# Canaux.net
KiCad netlist of a schematic drawn in Altium Designer
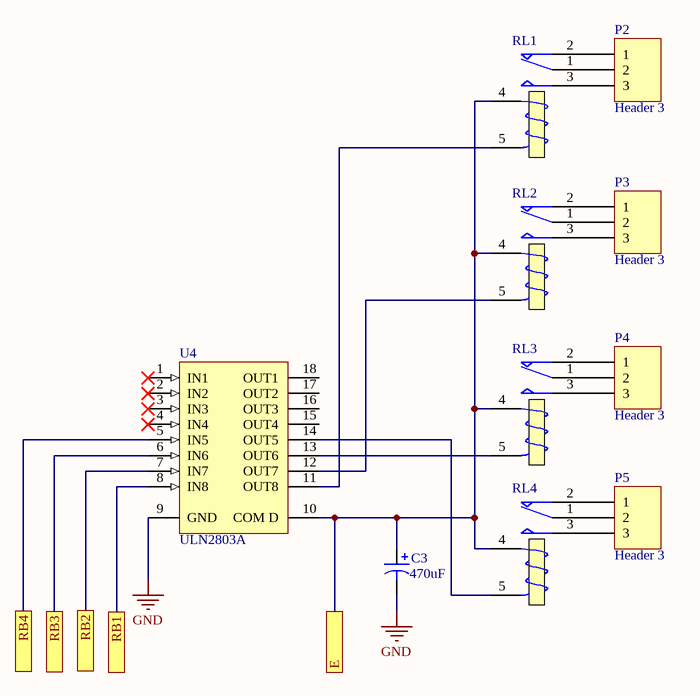
[diagram p0: Canaux.SchDoc]

(export (version "E")
  (design (tool "Eeschema 10.0.6"))
  (components
    (comp (ref "C3")
      (value "470uF")
      (footprint "RB7.6-15")
      (description "Polarized Capacitor (Radial)")
      (fields (field (name "Comment") "Cap Pol1") (field (name "PUBLISHER") "Altium Limited"))
      (libsource (lib "Miscellaneous Devices") (part "Cap Pol1"))
    )
    (comp (ref "P2")
      (value "Header 3")
      (footprint "HDR1X3")
      (description "Header, 3-Pin")
      (fields (field (name "PUBLISHER") "Altium Limited"))
      (libsource (lib "Miscellaneous Connectors") (part "Header 3"))
    )
    (comp (ref "P3")
      (value "Header 3")
      (footprint "HDR1X3")
      (description "Header, 3-Pin")
      (fields (field (name "PUBLISHER") "Altium Limited"))
      (libsource (lib "Miscellaneous Connectors") (part "Header 3"))
    )
    (comp (ref "P4")
      (value "Header 3")
      (footprint "HDR1X3")
      (description "Header, 3-Pin")
      (fields (field (name "PUBLISHER") "Altium Limited"))
      (libsource (lib "Miscellaneous Connectors") (part "Header 3"))
    )
    (comp (ref "P5")
      (value "Header 3")
      (footprint "HDR1X3")
      (description "Header, 3-Pin")
      (fields (field (name "PUBLISHER") "Altium Limited"))
      (libsource (lib "Miscellaneous Connectors") (part "Header 3"))
    )
    (comp (ref "RL1")
      (value "Relay")
      (footprint "MODULE5B")
      (description "SPDT Relay")
      (fields (field (name "PUBLISHER") "Altium Limited"))
      (libsource (lib "Miscellaneous Devices") (part "Relay"))
    )
    (comp (ref "RL2")
      (value "Relay")
      (footprint "MODULE5B")
      (description "SPDT Relay")
      (fields (field (name "PUBLISHER") "Altium Limited"))
      (libsource (lib "Miscellaneous Devices") (part "Relay"))
    )
    (comp (ref "RL3")
      (value "Relay")
      (footprint "MODULE5B")
      (description "SPDT Relay")
      (fields (field (name "PUBLISHER") "Altium Limited"))
      (libsource (lib "Miscellaneous Devices") (part "Relay"))
    )
    (comp (ref "RL4")
      (value "Relay")
      (footprint "MODULE5B")
      (description "SPDT Relay")
      (fields (field (name "PUBLISHER") "Altium Limited"))
      (libsource (lib "Miscellaneous Devices") (part "Relay"))
    )
    (comp (ref "U4")
      (value "ULN2803A")
      (footprint "A18")
      (description "High-Voltage, High-Current Darlington Array")
      (fields (field (name "PUBLISHER") "Altium Limited"))
      (libsource (lib "Allegro Interface Darlington Driver") (part "ULN2803A"))
    )
  )
  (nets
    (net (code "1") (name "/E") (class "Default")
      (node (ref "C3") (pin "1") (pinfunction "1_1") (pintype "passive"))
      (node (ref "RL1") (pin "4") (pinfunction "T1_4") (pintype "passive"))
      (node (ref "RL2") (pin "4") (pinfunction "T1_4") (pintype "passive"))
      (node (ref "RL3") (pin "4") (pinfunction "T1_4") (pintype "passive"))
      (node (ref "RL4") (pin "4") (pinfunction "T1_4") (pintype "passive"))
      (node (ref "U4") (pin "10") (pinfunction "COM_D_10") (pintype "passive"))
    )
    (net (code "2") (name "/RB1") (class "Default")
      (node (ref "U4") (pin "8") (pinfunction "IN8_8") (pintype "input"))
    )
    (net (code "3") (name "/RB2") (class "Default")
      (node (ref "U4") (pin "7") (pinfunction "IN7_7") (pintype "input"))
    )
    (net (code "4") (name "/RB3") (class "Default")
      (node (ref "U4") (pin "6") (pinfunction "IN6_6") (pintype "input"))
    )
    (net (code "5") (name "/RB4") (class "Default")
      (node (ref "U4") (pin "5") (pinfunction "IN5_5") (pintype "input"))
    )
    (net (code "6") (name "GND") (class "Default")
      (node (ref "C3") (pin "2") (pinfunction "2_2") (pintype "passive"))
      (node (ref "U4") (pin "9") (pinfunction "GND_9") (pintype "power_in"))
    )
    (net (code "7") (name "Net-(RL1-COM)") (class "Default")
      (node (ref "P2") (pin "2") (pinfunction "2_2") (pintype "passive"))
      (node (ref "RL1") (pin "1") (pinfunction "COM_1") (pintype "passive"))
    )
    (net (code "8") (name "Net-(RL1-NC)") (class "Default")
      (node (ref "P2") (pin "1") (pinfunction "1_1") (pintype "passive"))
      (node (ref "RL1") (pin "2") (pinfunction "NC_2") (pintype "passive"))
    )
    (net (code "9") (name "Net-(RL1-NO)") (class "Default")
      (node (ref "P2") (pin "3") (pinfunction "3_3") (pintype "passive"))
      (node (ref "RL1") (pin "3") (pinfunction "NO_3") (pintype "passive"))
    )
    (net (code "10") (name "Net-(RL1-T2)") (class "Default")
      (node (ref "RL1") (pin "5") (pinfunction "T2_5") (pintype "passive"))
      (node (ref "U4") (pin "11") (pinfunction "OUT8_11") (pintype "open_collector"))
    )
    (net (code "11") (name "Net-(RL2-COM)") (class "Default")
      (node (ref "P3") (pin "2") (pinfunction "2_2") (pintype "passive"))
      (node (ref "RL2") (pin "1") (pinfunction "COM_1") (pintype "passive"))
    )
    (net (code "12") (name "Net-(RL2-NC)") (class "Default")
      (node (ref "P3") (pin "1") (pinfunction "1_1") (pintype "passive"))
      (node (ref "RL2") (pin "2") (pinfunction "NC_2") (pintype "passive"))
    )
    (net (code "13") (name "Net-(RL2-NO)") (class "Default")
      (node (ref "P3") (pin "3") (pinfunction "3_3") (pintype "passive"))
      (node (ref "RL2") (pin "3") (pinfunction "NO_3") (pintype "passive"))
    )
    (net (code "14") (name "Net-(RL2-T2)") (class "Default")
      (node (ref "RL2") (pin "5") (pinfunction "T2_5") (pintype "passive"))
      (node (ref "U4") (pin "12") (pinfunction "OUT7_12") (pintype "open_collector"))
    )
    (net (code "15") (name "Net-(RL3-COM)") (class "Default")
      (node (ref "P4") (pin "2") (pinfunction "2_2") (pintype "passive"))
      (node (ref "RL3") (pin "1") (pinfunction "COM_1") (pintype "passive"))
    )
    (net (code "16") (name "Net-(RL3-NC)") (class "Default")
      (node (ref "P4") (pin "1") (pinfunction "1_1") (pintype "passive"))
      (node (ref "RL3") (pin "2") (pinfunction "NC_2") (pintype "passive"))
    )
    (net (code "17") (name "Net-(RL3-NO)") (class "Default")
      (node (ref "P4") (pin "3") (pinfunction "3_3") (pintype "passive"))
      (node (ref "RL3") (pin "3") (pinfunction "NO_3") (pintype "passive"))
    )
    (net (code "18") (name "Net-(RL3-T2)") (class "Default")
      (node (ref "RL3") (pin "5") (pinfunction "T2_5") (pintype "passive"))
      (node (ref "U4") (pin "13") (pinfunction "OUT6_13") (pintype "open_collector"))
    )
    (net (code "19") (name "Net-(RL4-COM)") (class "Default")
      (node (ref "P5") (pin "2") (pinfunction "2_2") (pintype "passive"))
      (node (ref "RL4") (pin "1") (pinfunction "COM_1") (pintype "passive"))
    )
    (net (code "20") (name "Net-(RL4-NC)") (class "Default")
      (node (ref "P5") (pin "1") (pinfunction "1_1") (pintype "passive"))
      (node (ref "RL4") (pin "2") (pinfunction "NC_2") (pintype "passive"))
    )
    (net (code "21") (name "Net-(RL4-NO)") (class "Default")
      (node (ref "P5") (pin "3") (pinfunction "3_3") (pintype "passive"))
      (node (ref "RL4") (pin "3") (pinfunction "NO_3") (pintype "passive"))
    )
    (net (code "22") (name "Net-(RL4-T2)") (class "Default")
      (node (ref "RL4") (pin "5") (pinfunction "T2_5") (pintype "passive"))
      (node (ref "U4") (pin "14") (pinfunction "OUT5_14") (pintype "open_collector"))
    )
    (net (code "23") (name "unconnected-(U4-IN1-Pad1)") (class "Default")
      (node (ref "U4") (pin "1") (pinfunction "IN1_1") (pintype "input+no_connect"))
    )
    (net (code "24") (name "unconnected-(U4-IN2-Pad2)") (class "Default")
      (node (ref "U4") (pin "2") (pinfunction "IN2_2") (pintype "input+no_connect"))
    )
    (net (code "25") (name "unconnected-(U4-IN3-Pad3)") (class "Default")
      (node (ref "U4") (pin "3") (pinfunction "IN3_3") (pintype "input+no_connect"))
    )
    (net (code "26") (name "unconnected-(U4-IN4-Pad4)") (class "Default")
      (node (ref "U4") (pin "4") (pinfunction "IN4_4") (pintype "input+no_connect"))
    )
    (net (code "27") (name "unconnected-(U4-OUT1-Pad18)") (class "Default")
      (node (ref "U4") (pin "18") (pinfunction "OUT1_18") (pintype "open_collector"))
    )
    (net (code "28") (name "unconnected-(U4-OUT2-Pad17)") (class "Default")
      (node (ref "U4") (pin "17") (pinfunction "OUT2_17") (pintype "open_collector"))
    )
    (net (code "29") (name "unconnected-(U4-OUT3-Pad16)") (class "Default")
      (node (ref "U4") (pin "16") (pinfunction "OUT3_16") (pintype "open_collector"))
    )
    (net (code "30") (name "unconnected-(U4-OUT4-Pad15)") (class "Default")
      (node (ref "U4") (pin "15") (pinfunction "OUT4_15") (pintype "open_collector"))
    )
  )
)
